# main_controller.net
KiCad netlist of a schematic drawn in Altium Designer
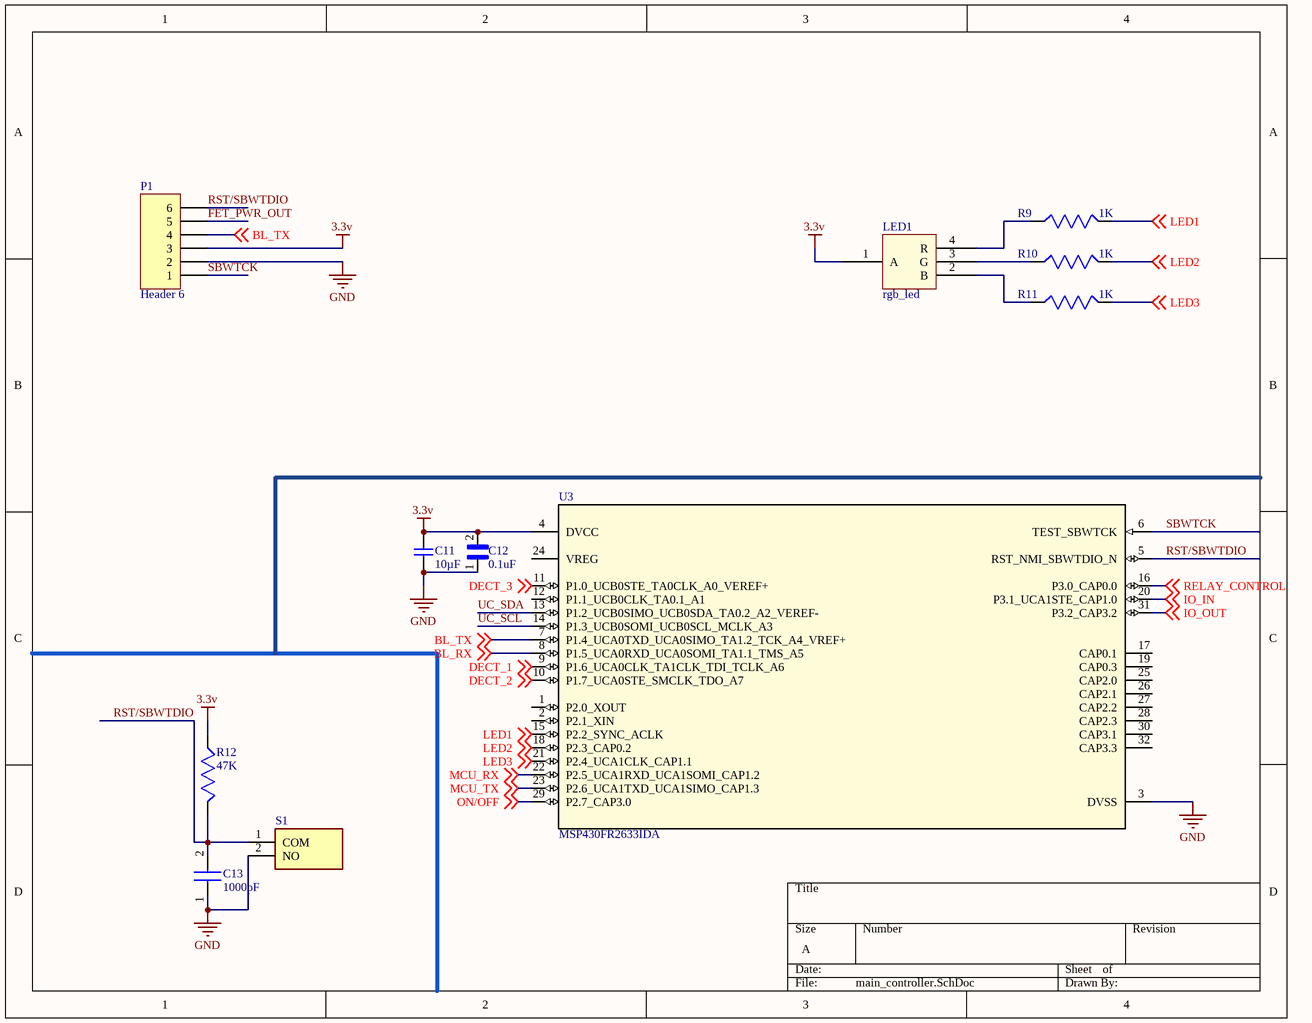
[diagram p0: main_controller.SchDoc]

(export (version "E")
  (design (tool "Eeschema 10.0.6"))
  (components
    (comp (ref "C11")
      (value "10µF")
      (footprint "CAP_0603")
      (description "10µF 10V Ceramic Capacitor X5R 0603 (1608 Metric) 0.063\" L x 0.031\" W (1.60mm x 0.80mm)")
      (fields
        (field (name "MANUFACTURER") "Samsung Electronics")
        (field (name "PART NUMBER") "CL10A106KP8NNNC")
      )
      (libsource (lib "apollo2-amaph1kk-kbr-brd") (part "CL10A106KP8NNNC"))
    )
    (comp (ref "C12")
      (value "0.1uF")
      (footprint "CAPC1608X90N")
      (description "Cap Ceramic 0.1uF 25V Y5V -20% to 80% SMD 0603 85C T/R")
      (fields (field (name "MP") "06033G104ZAT4A") (field (name "MF") "{'manufacturer': u'AVX'}"))
      (libsource (lib "chargebot_alpha") (part "06033G104ZAT4A"))
    )
    (comp (ref "C13")
      (value "1000pF")
      (footprint "mouser_layout_lib:CAPC1608X90N")
      (description "Capacitor")
      (fields
        (field (name "MANUFACTURER_PART_NUMBER") "06035C102KAT4A")
        (field (name "MOUSER PART NUMBER") "581-06035C102KAT4A")
      )
      (libsource (lib "*") (part "06035C102KAT4A"))
    )
    (comp (ref "LED1")
      (value "rgb_led")
      (footprint "SOP4")
      (libsource (lib "chargebot_alpha") (part "rgb_led"))
    )
    (comp (ref "P1")
      (value "Header 6")
      (footprint "HDR1X6")
      (description "Header, 6-Pin")
      (fields (field (name "PUBLISHER") "Altium Limited"))
      (libsource (lib "Miscellaneous Connectors") (part "Header 6"))
    )
    (comp (ref "R9")
      (value "1K")
      (footprint "RESC1508X50N")
      (description "RC Series 0603 0.1 W 47 kOhms 1% Â±100 ppm/Â°C SMT Thick Film Chip Resistor")
      (fields (field (name "MP") "RC0603FR-0747KL") (field (name "MF") "{'manufacturer': u'Yageo'}"))
      (libsource (lib "SnapEDA_Library") (part "RC0603FR-0747KL"))
    )
    (comp (ref "R10")
      (value "1K")
      (footprint "RESC1508X50N")
      (description "RC Series 0603 0.1 W 47 kOhms 1% Â±100 ppm/Â°C SMT Thick Film Chip Resistor")
      (fields (field (name "MP") "RC0603FR-0747KL") (field (name "MF") "{'manufacturer': u'Yageo'}"))
      (libsource (lib "SnapEDA_Library") (part "RC0603FR-0747KL"))
    )
    (comp (ref "R11")
      (value "1K")
      (footprint "RESC1508X50N")
      (description "RC Series 0603 0.1 W 47 kOhms 1% Â±100 ppm/Â°C SMT Thick Film Chip Resistor")
      (fields (field (name "MP") "RC0603FR-0747KL") (field (name "MF") "{'manufacturer': u'Yageo'}"))
      (libsource (lib "SnapEDA_Library") (part "RC0603FR-0747KL"))
    )
    (comp (ref "R12")
      (value "47K")
      (footprint "RESC1608X55")
      (description "RC Series 0603 0.1 W 47 kOhms 1% Â±100 ppm/Â°C SMT Thick Film Chip Resistor")
      (fields (field (name "MP") "RC0603FR-0747KL") (field (name "MF") "{'manufacturer': u'Yageo'}"))
      (libsource (lib "SnapEDA_Library") (part "RC0603FR-0747KL"))
    )
    (comp (ref "S1")
      (value "PTS636_SM43_SMTR_LFS")
      (footprint "PTS636SM43SMTRLFS")
      (description "Switch")
      (fields
        (field (name "MANUFACTURER_PART_NUMBER") "PTS636 SM43 SMTR LFS")
        (field (name "MOUSER PART NUMBER") "611-PTS636SM43SMTRLF")
      )
      (libsource (lib "mouser_sch_lib") (part "PTS636_SM43_SMTR_LFS"))
    )
    (comp (ref "U3")
      (value "MSP430FR2633IDA")
      (footprint "DA0032A_L")
      (description "No Description Available")
      (fields
        (field (name "PARTNUMBER") "MSP430FR2633IDAR")
        (field (name "MANUFACTURER") "Texas Instruments")
        (field (name "COPYRIGHT") "Copyright (C) 2022 Ultra Librarian. All rights reserved.")
      )
      (libsource (lib "MSP430FR2633IDA") (part "MSP430FR2633IDA"))
    )
  )
  (nets
    (net (code "1") (name "/FET_PWR_OUT") (class "Default")
      (node (ref "P1") (pin "5") (pinfunction "5_5") (pintype "passive"))
    )
    (net (code "2") (name "/RST{slash}SBWTDIO") (class "Default")
      (node (ref "C13") (pin "2") (pinfunction "2_2") (pintype "passive"))
      (node (ref "P1") (pin "6") (pinfunction "6_6") (pintype "passive"))
      (node (ref "R12") (pin "1") (pinfunction "1_1") (pintype "passive"))
      (node (ref "S1") (pin "1") (pinfunction "COM_1") (pintype "passive"))
      (node (ref "U3") (pin "5") (pinfunction "RST_NMI_SBWTDIO_N_5") (pintype "bidirectional"))
    )
    (net (code "3") (name "/SBWTCK") (class "Default")
      (node (ref "P1") (pin "1") (pinfunction "1_1") (pintype "passive"))
      (node (ref "U3") (pin "6") (pinfunction "TEST_SBWTCK_6") (pintype "input"))
    )
    (net (code "4") (name "/UC_SCL") (class "Default")
      (node (ref "U3") (pin "14") (pinfunction "P1.3_UCB0SOMI_UCB0SCL_MCLK_A3_14") (pintype "bidirectional"))
    )
    (net (code "5") (name "/UC_SDA") (class "Default")
      (node (ref "U3") (pin "13") (pinfunction "P1.2_UCB0SIMO_UCB0SDA_TA0.2_A2_VEREF-_13") (pintype "bidirectional"))
    )
    (net (code "6") (name "3.3v") (class "Default")
      (node (ref "C11") (pin "1") (pinfunction "1_1") (pintype "passive"))
      (node (ref "C12") (pin "2") (pinfunction "2_2") (pintype "passive"))
      (node (ref "LED1") (pin "1") (pinfunction "A_1") (pintype "passive"))
      (node (ref "P1") (pin "3") (pinfunction "3_3") (pintype "passive"))
      (node (ref "R12") (pin "2") (pinfunction "2_2") (pintype "passive"))
      (node (ref "U3") (pin "4") (pinfunction "DVCC_4") (pintype "power_in"))
    )
    (net (code "7") (name "BL_RX") (class "Default")
      (node (ref "U3") (pin "8") (pinfunction "P1.5_UCA0RXD_UCA0SOMI_TA1.1_TMS_A5_8") (pintype "bidirectional"))
    )
    (net (code "8") (name "BL_TX") (class "Default")
      (node (ref "P1") (pin "4") (pinfunction "4_4") (pintype "passive"))
      (node (ref "U3") (pin "7") (pinfunction "P1.4_UCA0TXD_UCA0SIMO_TA1.2_TCK_A4_VREF+_7") (pintype "bidirectional"))
    )
    (net (code "9") (name "DECT_1") (class "Default")
      (node (ref "U3") (pin "9") (pinfunction "P1.6_UCA0CLK_TA1CLK_TDI_TCLK_A6_9") (pintype "bidirectional"))
    )
    (net (code "10") (name "DECT_2") (class "Default")
      (node (ref "U3") (pin "10") (pinfunction "P1.7_UCA0STE_SMCLK_TDO_A7_10") (pintype "bidirectional"))
    )
    (net (code "11") (name "DECT_3") (class "Default")
      (node (ref "U3") (pin "11") (pinfunction "P1.0_UCB0STE_TA0CLK_A0_VEREF+_11") (pintype "bidirectional"))
    )
    (net (code "12") (name "GND") (class "Default")
      (node (ref "C11") (pin "2") (pinfunction "2_2") (pintype "passive"))
      (node (ref "C12") (pin "1") (pinfunction "1_1") (pintype "passive"))
      (node (ref "C13") (pin "1") (pinfunction "1_1") (pintype "passive"))
      (node (ref "P1") (pin "2") (pinfunction "2_2") (pintype "passive"))
      (node (ref "S1") (pin "2") (pinfunction "NO_2") (pintype "passive"))
      (node (ref "U3") (pin "3") (pinfunction "DVSS_3") (pintype "power_in"))
    )
    (net (code "13") (name "IO_IN") (class "Default")
      (node (ref "U3") (pin "20") (pinfunction "P3.1_UCA1STE_CAP1.0_20") (pintype "bidirectional"))
    )
    (net (code "14") (name "IO_OUT") (class "Default")
      (node (ref "U3") (pin "31") (pinfunction "P3.2_CAP3.2_31") (pintype "bidirectional"))
    )
    (net (code "15") (name "LED1") (class "Default")
      (node (ref "R9") (pin "1") (pinfunction "1_1") (pintype "passive"))
      (node (ref "U3") (pin "15") (pinfunction "P2.2_SYNC_ACLK_15") (pintype "bidirectional"))
    )
    (net (code "16") (name "LED2") (class "Default")
      (node (ref "R10") (pin "1") (pinfunction "1_1") (pintype "passive"))
      (node (ref "U3") (pin "18") (pinfunction "P2.3_CAP0.2_18") (pintype "bidirectional"))
    )
    (net (code "17") (name "LED3") (class "Default")
      (node (ref "R11") (pin "1") (pinfunction "1_1") (pintype "passive"))
      (node (ref "U3") (pin "21") (pinfunction "P2.4_UCA1CLK_CAP1.1_21") (pintype "bidirectional"))
    )
    (net (code "18") (name "MCU_RX") (class "Default")
      (node (ref "U3") (pin "22") (pinfunction "P2.5_UCA1RXD_UCA1SOMI_CAP1.2_22") (pintype "bidirectional"))
    )
    (net (code "19") (name "MCU_TX") (class "Default")
      (node (ref "U3") (pin "23") (pinfunction "P2.6_UCA1TXD_UCA1SIMO_CAP1.3_23") (pintype "bidirectional"))
    )
    (net (code "20") (name "Net-(LED1-B)") (class "Default")
      (node (ref "LED1") (pin "2") (pinfunction "B_2") (pintype "passive"))
      (node (ref "R11") (pin "2") (pinfunction "2_2") (pintype "passive"))
    )
    (net (code "21") (name "Net-(LED1-G)") (class "Default")
      (node (ref "LED1") (pin "3") (pinfunction "G_3") (pintype "passive"))
      (node (ref "R10") (pin "2") (pinfunction "2_2") (pintype "passive"))
    )
    (net (code "22") (name "Net-(LED1-R)") (class "Default")
      (node (ref "LED1") (pin "4") (pinfunction "R_4") (pintype "passive"))
      (node (ref "R9") (pin "2") (pinfunction "2_2") (pintype "passive"))
    )
    (net (code "23") (name "ON{slash}OFF") (class "Default")
      (node (ref "U3") (pin "29") (pinfunction "P2.7_CAP3.0_29") (pintype "bidirectional"))
    )
    (net (code "24") (name "RELAY_CONTROL") (class "Default")
      (node (ref "U3") (pin "16") (pinfunction "P3.0_CAP0.0_16") (pintype "bidirectional"))
    )
    (net (code "25") (name "unconnected-(U3-CAP0.1-Pad17)") (class "Default")
      (node (ref "U3") (pin "17") (pinfunction "CAP0.1_17") (pintype "passive"))
    )
    (net (code "26") (name "unconnected-(U3-CAP0.3-Pad19)") (class "Default")
      (node (ref "U3") (pin "19") (pinfunction "CAP0.3_19") (pintype "passive"))
    )
    (net (code "27") (name "unconnected-(U3-CAP2.0-Pad25)") (class "Default")
      (node (ref "U3") (pin "25") (pinfunction "CAP2.0_25") (pintype "passive"))
    )
    (net (code "28") (name "unconnected-(U3-CAP2.1-Pad26)") (class "Default")
      (node (ref "U3") (pin "26") (pinfunction "CAP2.1_26") (pintype "passive"))
    )
    (net (code "29") (name "unconnected-(U3-CAP2.2-Pad27)") (class "Default")
      (node (ref "U3") (pin "27") (pinfunction "CAP2.2_27") (pintype "passive"))
    )
    (net (code "30") (name "unconnected-(U3-CAP2.3-Pad28)") (class "Default")
      (node (ref "U3") (pin "28") (pinfunction "CAP2.3_28") (pintype "passive"))
    )
    (net (code "31") (name "unconnected-(U3-CAP3.1-Pad30)") (class "Default")
      (node (ref "U3") (pin "30") (pinfunction "CAP3.1_30") (pintype "passive"))
    )
    (net (code "32") (name "unconnected-(U3-CAP3.3-Pad32)") (class "Default")
      (node (ref "U3") (pin "32") (pinfunction "CAP3.3_32") (pintype "passive"))
    )
    (net (code "33") (name "unconnected-(U3-P1.1_UCB0CLK_TA0.1_A1-Pad12)") (class "Default")
      (node (ref "U3") (pin "12") (pinfunction "P1.1_UCB0CLK_TA0.1_A1_12") (pintype "bidirectional"))
    )
    (net (code "34") (name "unconnected-(U3-P2.0_XOUT-Pad1)") (class "Default")
      (node (ref "U3") (pin "1") (pinfunction "P2.0_XOUT_1") (pintype "bidirectional"))
    )
    (net (code "35") (name "unconnected-(U3-P2.1_XIN-Pad2)") (class "Default")
      (node (ref "U3") (pin "2") (pinfunction "P2.1_XIN_2") (pintype "bidirectional"))
    )
    (net (code "36") (name "unconnected-(U3-VREG-Pad24)") (class "Default")
      (node (ref "U3") (pin "24") (pinfunction "VREG_24") (pintype "power_in"))
    )
  )
)
